# Motor_Control.net
KiCad netlist of a schematic drawn in Altium Designer
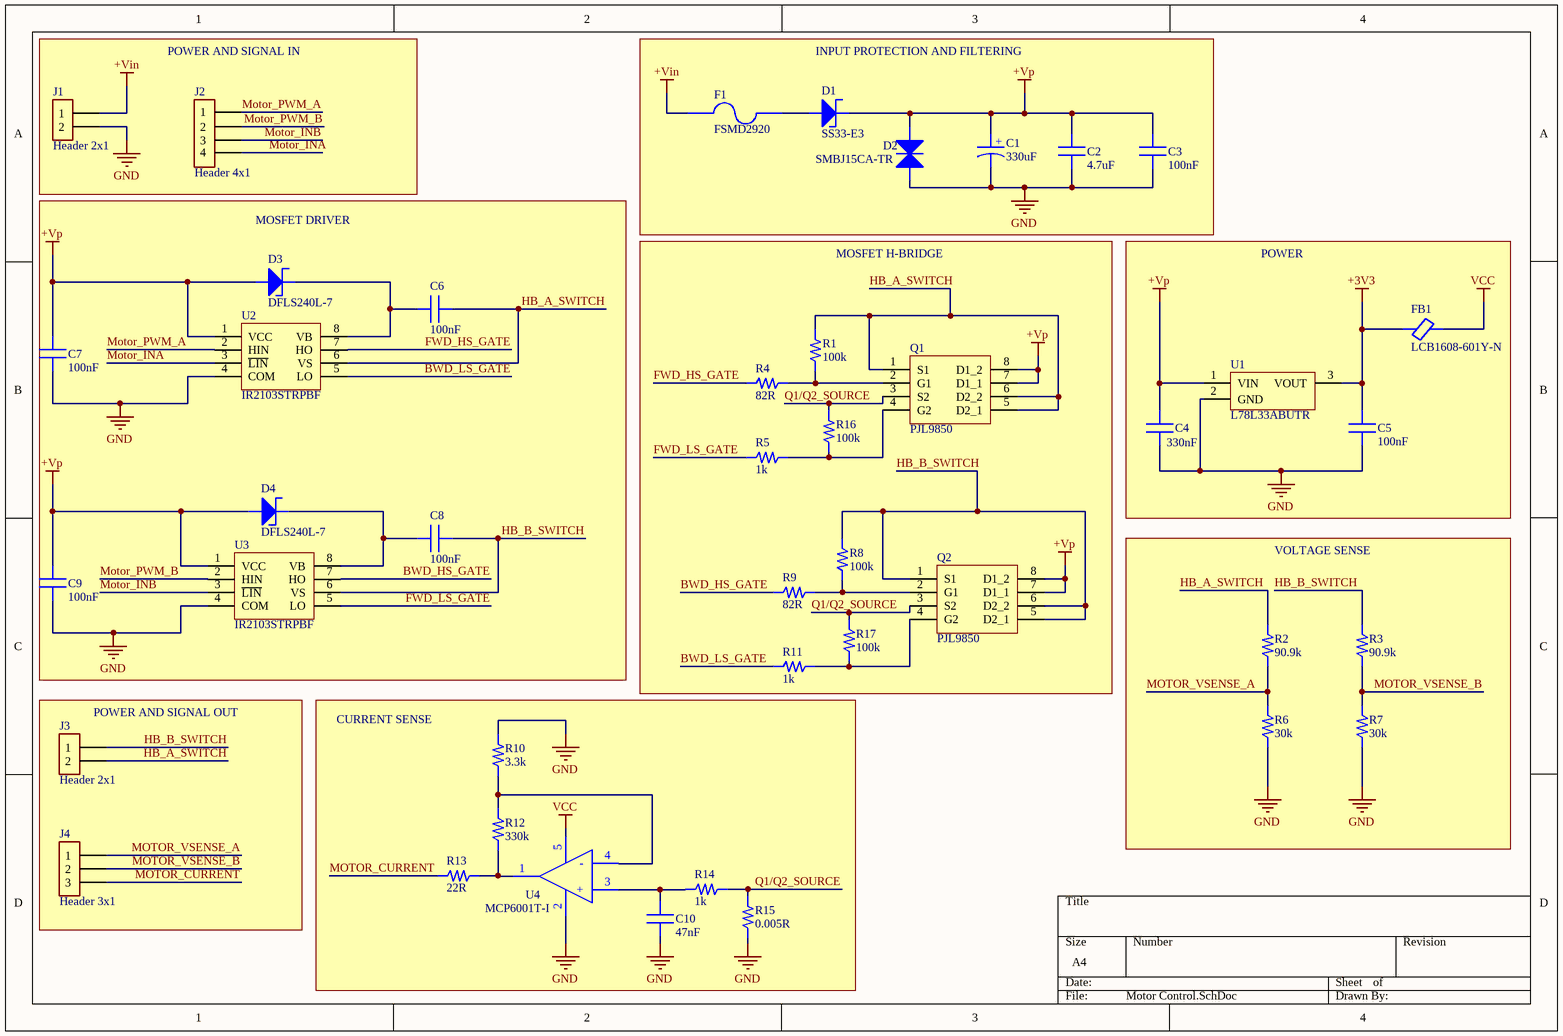
[diagram p0: Motor Control.SchDoc]

(export (version "E")
  (design (tool "Eeschema 10.0.6"))
  (components
    (comp (ref "C1")
      (value "330uF")
      (footprint "CAP_EEEFK1V331P")
      (description "330 µF 35 V Aluminum Electrolytic Capacitors Radial, Can - SMD 2000 Hrs @ 105°C")
      (fields (field (name "TOLERANCE") "±20%") (field (name "MANUFACTURER") "Panasonic Industry"))
      (libsource (lib "Chicken_Coop_Door_Main_Board_V3") (part "CAP Electrolytic EEE-FK1V331P"))
    )
    (comp (ref "C2")
      (value "4.7uF")
      (footprint "CAPC2012X145N 0805")
      (description "MLCC (2012) 0805 4.7uF 16VDC ±10% X7R AUTOMOTIVE")
      (fields (field (name "TOLERANCE") "±10 %") (field (name "MANUFACTURER") "SAMSUNG"))
      (libsource (lib "Chicken_Coop_Door_Main_Board_V3") (part "CAP 0805 4.7uF CL21B475KOQVPNE"))
    )
    (comp (ref "C3")
      (value "100nF")
      (footprint "CAPC2012X145N 0805")
      (description "MLCC 0805 100nF 50VDC ±10% X7R")
      (fields (field (name "TOLERANCE") "±5 %") (field (name "MANUFACTURER") "YAGEO"))
      (libsource (lib "Chicken_Coop_Door_Main_Board_V3") (part "CAP 0805 100nF CC0805JRX7R9BB104"))
    )
    (comp (ref "C4")
      (value "330nF")
      (footprint "CAPC2012X145N 0805")
      (description "MLCC (2012) 0805 330nF 50VDC ±10% X7R")
      (fields (field (name "TOLERANCE") "±10 %") (field (name "MANUFACTURER") "SAMSUNG"))
      (libsource (lib "Chicken_Coop_Door_Main_Board_V3") (part "CAP 0805 330nF CL21B334KBFNNNE"))
    )
    (comp (ref "C5")
      (value "100nF")
      (footprint "CAPC2012X145N 0805")
      (description "MLCC 0805 100nF 50VDC ±10% X7R")
      (fields (field (name "TOLERANCE") "±5 %") (field (name "MANUFACTURER") "YAGEO"))
      (libsource (lib "Chicken_Coop_Door_Main_Board_V3") (part "CAP 0805 100nF CC0805JRX7R9BB104"))
    )
    (comp (ref "C6")
      (value "100nF")
      (footprint "CAPC2012X145N 0805")
      (description "MLCC 0805 100nF 50VDC ±10% X7R")
      (fields (field (name "TOLERANCE") "±5 %") (field (name "MANUFACTURER") "YAGEO"))
      (libsource (lib "Chicken_Coop_Door_Main_Board_V3") (part "CAP 0805 100nF CC0805JRX7R9BB104"))
    )
    (comp (ref "C7")
      (value "100nF")
      (footprint "CAPC2012X145N 0805")
      (description "MLCC 0805 100nF 50VDC ±10% X7R")
      (fields (field (name "TOLERANCE") "±5 %") (field (name "MANUFACTURER") "YAGEO"))
      (libsource (lib "Chicken_Coop_Door_Main_Board_V3") (part "CAP 0805 100nF CC0805JRX7R9BB104"))
    )
    (comp (ref "C8")
      (value "100nF")
      (footprint "CAPC2012X145N 0805")
      (description "MLCC 0805 100nF 50VDC ±10% X7R")
      (fields (field (name "TOLERANCE") "±5 %") (field (name "MANUFACTURER") "YAGEO"))
      (libsource (lib "Chicken_Coop_Door_Main_Board_V3") (part "CAP 0805 100nF CC0805JRX7R9BB104"))
    )
    (comp (ref "C9")
      (value "100nF")
      (footprint "CAPC2012X145N 0805")
      (description "MLCC 0805 100nF 50VDC ±10% X7R")
      (fields (field (name "TOLERANCE") "±5 %") (field (name "MANUFACTURER") "YAGEO"))
      (libsource (lib "Chicken_Coop_Door_Main_Board_V3") (part "CAP 0805 100nF CC0805JRX7R9BB104"))
    )
    (comp (ref "C10")
      (value "47nF")
      (footprint "CAPC2012X145N 0805")
      (description "CL21B473KBCNNNC")
      (fields (field (name "TOLERANCE") "±10 %") (field (name "MANUFACTURER") "SAMSUNG"))
      (libsource (lib "Chicken_Coop_Door_Main_Board_V3") (part "CAP 0805 47nF CL21B473KBCNNNC"))
    )
    (comp (ref "D1")
      (value "SS33-E3")
      (footprint "SS33-E3/57T Schottky Diode")
      (description "DIODE SCHOTTKY 30V 3A DO214AB")
      (fields (field (name "MANUFACTURER") "Vishay General Semiconductor - Diodes Division"))
      (libsource (lib "Chicken_Coop_Door_Main_Board_V3") (part "DIODE SCHOTTKY SS33-E3/57T"))
    )
    (comp (ref "D2")
      (value "SMBJ15CA-TR")
      (footprint "TVS DIODE SMBJ15CA-TR")
      (description "24.4V Clamp 25.1A Ipp Tvs Diode Surface Mount SMB")
      (fields (field (name "MANUFACTURER") "STMicroelectronics"))
      (libsource (lib "Chicken_Coop_Door_Main_Board_V3") (part "TVS DIODE SMBJ15CA-TR"))
    )
    (comp (ref "D3")
      (value "DFLS240L-7")
      (footprint "DIODE DFLS240L-7  POWERDI 123")
      (description "DIODE SCHOTTK 40V 2A POWERDI 123")
      (fields (field (name "MANUFACTURER") "Diodes Incorporated"))
      (libsource (lib "Chicken_Coop_Door_Main_Board_V3") (part "DIODE SCHOTTKY DFLS240L-7"))
    )
    (comp (ref "D4")
      (value "DFLS240L-7")
      (footprint "DIODE DFLS240L-7  POWERDI 123")
      (description "DIODE SCHOTTK 40V 2A POWERDI 123")
      (fields (field (name "MANUFACTURER") "Diodes Incorporated"))
      (libsource (lib "Chicken_Coop_Door_Main_Board_V3") (part "DIODE SCHOTTKY DFLS240L-7"))
    )
    (comp (ref "F1")
      (value "FSMD2920")
      (footprint "FUSE FSMD200-24-2920-R")
      (description "PTC Resettable Fuse 24V 2 A Ih Surface Mount 2920 (7351 Metric), Concave")
      (fields (field (name "MANUFACTURER") "RFE/Fuzetec"))
      (libsource (lib "Chicken_Coop_Door_Main_Board_V3") (part "FUSE FSMD200-24-2920-R"))
    )
    (comp (ref "FB1")
      (value "LCB1608-601Y-N")
      (footprint "MPZ1608S601ATA00 0603 1608X95N")
      (description "600 Ohms @ 100 MHz 1 Power Line Ferrite Bead 0603 (1608 Metric) 1A 200mOhm")
      (fields (field (name "TOLERANCE") "±25 %") (field (name "MANUFACTURER") "CORE MASTER"))
      (libsource (lib "Chicken_Coop_Door_Main_Board_V3") (part "Ferrite Bead LCB1608-601Y-N"))
    )
    (comp (ref "J1")
      (value "Header 2x1")
      (footprint "2x1 Terminal Block")
      (description "TERM.BLK.5.00MM 2P PCB TYPE GREEN")
      (fields (field (name "MANUFACTURER") "DEGSON") (field (name "VOLTAGE") "300V"))
      (libsource (lib "Chicken_Coop_Door_Main_Board_V3") (part "Terminal Block 2x1"))
    )
    (comp (ref "J2")
      (value "Header 4x1")
      (footprint "JST_B4B-PH-K-S 1x4 Header")
      (description "CON.T.B.2MM 4P 180C MALE WHITE CONNFLY")
      (fields (field (name "MANUFACTURER") "CONNFLY"))
      (libsource (lib "Chicken_Coop_Door_Main_Board_V3") (part "Header 4x1 DS1066-4MVW6X"))
    )
    (comp (ref "J3")
      (value "Header 2x1")
      (footprint "2x1 Terminal Block")
      (description "TERM.BLK.5.00MM 2P PCB TYPE GREEN")
      (fields (field (name "MANUFACTURER") "DEGSON") (field (name "VOLTAGE") "300V"))
      (libsource (lib "Chicken_Coop_Door_Main_Board_V3") (part "Terminal Block 2x1"))
    )
    (comp (ref "J4")
      (value "Header 3x1")
      (footprint "JST_B3B-PH-K-S 1x3 Header")
      (description "CON.T.B.2.00MM 3P 180C MALE CONNFLY")
      (fields (field (name "MANUFACTURER") "CONNFLY"))
      (libsource (lib "Chicken_Coop_Door_Main_Board_V3") (part "Header 3x1 DS1066-3MVW6X"))
    )
    (comp (ref "Q1")
      (value "PJL9850")
      (footprint "PJL850 N-CH MOSFET")
      (description "Low Voltage MOSFET (20-40V,Rds(on)<1) - PJL9850 , N/N Channel, Dual, 5.4A, 40V, SOP-8")
      (fields (field (name "MANUFACTURER") "PANJIT"))
      (libsource (lib "Chicken_Coop_Door_Main_Board_V3") (part "PJL9850 N-Ch MOSFET"))
    )
    (comp (ref "Q2")
      (value "PJL9850")
      (footprint "PJL850 N-CH MOSFET")
      (description "Low Voltage MOSFET (20-40V,Rds(on)<1) - PJL9850 , N/N Channel, Dual, 5.4A, 40V, SOP-8")
      (fields (field (name "MANUFACTURER") "PANJIT"))
      (libsource (lib "Chicken_Coop_Door_Main_Board_V3") (part "PJL9850 N-Ch MOSFET"))
    )
    (comp (ref "R1")
      (value "100k")
      (footprint "RES 0603 ROYALOHM")
      (description "RES.(1608) 0603 100K Ohms 1% 1/10W-S 100PPM")
      (fields (field (name "TOLERANCE") "±5 %") (field (name "MANUFACTURER") "ROYALOHM"))
      (libsource (lib "Chicken_Coop_Door_Main_Board_V3") (part "RES 0603 100k 0603SAF1003T5E"))
    )
    (comp (ref "R2")
      (value "90.9k")
      (footprint "RES 0805 YAGEO C2012X60N")
      (description "RES.(2012) 0805 90.9K Ohms 1% 1/8W-S 100PPM")
      (fields (field (name "POWER") "1/8W") (field (name "TOLERANCE") "±1 %"))
      (libsource (lib "Chicken_Coop_Door_Main_Board_V3") (part "RES 0805 90.9k Ohms 0805S8F9092T5E"))
    )
    (comp (ref "R3")
      (value "90.9k")
      (footprint "RES 0805 YAGEO C2012X60N")
      (description "RES.(2012) 0805 90.9K Ohms 1% 1/8W-S 100PPM")
      (fields (field (name "POWER") "1/8W") (field (name "TOLERANCE") "±1 %"))
      (libsource (lib "Chicken_Coop_Door_Main_Board_V3") (part "RES 0805 90.9k Ohms 0805S8F9092T5E"))
    )
    (comp (ref "R4")
      (value "82R")
      (footprint "RES 0805 YAGEO C2012X60N")
      (description "RES.(2012) 0805 82 Ohms 5% 1/8W-S 200PPM")
      (fields (field (name "POWER") "1/8W") (field (name "TOLERANCE") "±1 %"))
      (libsource (lib "Chicken_Coop_Door_Main_Board_V3") (part "RES 0805 82 Ohms 0805S8J0820T5E"))
    )
    (comp (ref "R5")
      (value "1k")
      (footprint "RES 0805 YAGEO C2012X60N")
      (description "RES.(2012) 0805 1K Ohms 1% 1/8W-S 100PPM")
      (fields (field (name "POWER") "1/8W") (field (name "TOLERANCE") "±1 %"))
      (libsource (lib "Chicken_Coop_Door_Main_Board_V3") (part "RES 0805 1k Ohms 0805S8F1001TDE"))
    )
    (comp (ref "R6")
      (value "30k")
      (footprint "RES 0805 YAGEO C2012X60N")
      (description "RES.(2012) 0805 30K Ohms 1% 1/8W-S 100PPM")
      (fields (field (name "POWER") "1/8W") (field (name "TOLERANCE") "±1 %"))
      (libsource (lib "Chicken_Coop_Door_Main_Board_V3") (part "RES 0805 30k Ohms 0805S8F3002T5E"))
    )
    (comp (ref "R7")
      (value "30k")
      (footprint "RES 0805 YAGEO C2012X60N")
      (description "RES.(2012) 0805 30K Ohms 1% 1/8W-S 100PPM")
      (fields (field (name "POWER") "1/8W") (field (name "TOLERANCE") "±1 %"))
      (libsource (lib "Chicken_Coop_Door_Main_Board_V3") (part "RES 0805 30k Ohms 0805S8F3002T5E"))
    )
    (comp (ref "R8")
      (value "100k")
      (footprint "RES 0603 ROYALOHM")
      (description "RES.(1608) 0603 100K Ohms 1% 1/10W-S 100PPM")
      (fields (field (name "TOLERANCE") "±5 %") (field (name "MANUFACTURER") "ROYALOHM"))
      (libsource (lib "Chicken_Coop_Door_Main_Board_V3") (part "RES 0603 100k 0603SAF1003T5E"))
    )
    (comp (ref "R9")
      (value "82R")
      (footprint "RES 0805 YAGEO C2012X60N")
      (description "RES.(2012) 0805 82 Ohms 5% 1/8W-S 200PPM")
      (fields (field (name "POWER") "1/8W") (field (name "TOLERANCE") "±1 %"))
      (libsource (lib "Chicken_Coop_Door_Main_Board_V3") (part "RES 0805 82 Ohms 0805S8J0820T5E"))
    )
    (comp (ref "R10")
      (value "3.3k")
      (footprint "RES 0805 YAGEO C2012X60N")
      (description "RES.(2012) 0805 3.3K Ohms 1% 1/8W-S 100PPM")
      (fields (field (name "POWER") "1/8W") (field (name "TOLERANCE") "±1 %"))
      (libsource (lib "Chicken_Coop_Door_Main_Board_V3") (part "RES 0805 3.3k Ohms 0805S8F3301TDE"))
    )
    (comp (ref "R11")
      (value "1k")
      (footprint "RES 0805 YAGEO C2012X60N")
      (description "RES.(2012) 0805 1K Ohms 1% 1/8W-S 100PPM")
      (fields (field (name "POWER") "1/8W") (field (name "TOLERANCE") "±1 %"))
      (libsource (lib "Chicken_Coop_Door_Main_Board_V3") (part "RES 0805 1k Ohms 0805S8F1001TDE"))
    )
    (comp (ref "R12")
      (value "330k")
      (footprint "RES 0603 ROYALOHM")
      (description "RES.(1608) 0603 330K Ohms 1% 1/10W-S 100PPM")
      (fields (field (name "TOLERANCE") "±5 %") (field (name "MANUFACTURER") "ROYALOHM"))
      (libsource (lib "Chicken_Coop_Door_Main_Board_V3") (part "RES 0603 330k 0603SAF3303T5E"))
    )
    (comp (ref "R13")
      (value "22R")
      (footprint "RES 0603 ROYALOHM")
      (description "RES.(1608) 0603 22 Ohms 5% 1/10W-S 200PPM")
      (fields (field (name "TOLERANCE") "±5%") (field (name "MANUFACTURER") "ROYALOHM"))
      (libsource (lib "Chicken_Coop_Door_Main_Board_V3") (part "RES 0603 22 Ohms 0603SAJ0220T5E"))
    )
    (comp (ref "R14")
      (value "1k")
      (footprint "RES 0805 YAGEO C2012X60N")
      (description "RES.(2012) 0805 1K Ohms 1% 1/8W-S 100PPM")
      (fields (field (name "POWER") "1/8W") (field (name "TOLERANCE") "±1 %"))
      (libsource (lib "Chicken_Coop_Door_Main_Board_V3") (part "RES 0805 1k Ohms 0805S8F1001TDE"))
    )
    (comp (ref "R15")
      (value "0.005R")
      (footprint "RES 1206 YAGEO")
      (description "RES.(3216) 1206 5m Ohms 1% 1/4W 100PPM AEC-Q200 SM")
      (fields (field (name "POWER") "1/4W") (field (name "TOLERANCE") "±1 %"))
      (libsource (lib "Chicken_Coop_Door_Main_Board_V3") (part "RES 1206 5 mOhms PE1206FRF070R005L"))
    )
    (comp (ref "R16")
      (value "100k")
      (footprint "RES 0603 ROYALOHM")
      (description "RES.(1608) 0603 100K Ohms 1% 1/10W-S 100PPM")
      (fields (field (name "TOLERANCE") "±5 %") (field (name "MANUFACTURER") "ROYALOHM"))
      (libsource (lib "Chicken_Coop_Door_Main_Board_V3") (part "RES 0603 100k 0603SAF1003T5E"))
    )
    (comp (ref "R17")
      (value "100k")
      (footprint "RES 0603 ROYALOHM")
      (description "RES.(1608) 0603 100K Ohms 1% 1/10W-S 100PPM")
      (fields (field (name "TOLERANCE") "±5 %") (field (name "MANUFACTURER") "ROYALOHM"))
      (libsource (lib "Chicken_Coop_Door_Main_Board_V3") (part "RES 0603 100k 0603SAF1003T5E"))
    )
    (comp (ref "U1")
      (value "L78L33ABUTR")
      (footprint "LDO L78L33ABUTR SOT89")
      (description "Linear Voltage Regulator IC Positive Fixed 1 Output 100mA SOT-89-3")
      (fields (field (name "MANUFACTURER") "STMicroelectronics"))
      (libsource (lib "Chicken_Coop_Door_Main_Board_V3") (part "LDO L78L33ABUTR"))
    )
    (comp (ref "U2")
      (value "IR2103STRPBF")
      (footprint "IR2103STRPBF Half Bridge Mosfet Driver")
      (description "Half-Bridge Gate Driver IC Inverting, Non-Inverting 8-SOIC")
      (fields (field (name "MANUFACTURER") "Infineon Technologies"))
      (libsource (lib "Chicken_Coop_Door_Main_Board_V3") (part "IR2103STRPBF Half Bridge MOSFET Driver"))
    )
    (comp (ref "U3")
      (value "IR2103STRPBF")
      (footprint "IR2103STRPBF Half Bridge Mosfet Driver")
      (description "Half-Bridge Gate Driver IC Inverting, Non-Inverting 8-SOIC")
      (fields (field (name "MANUFACTURER") "Infineon Technologies"))
      (libsource (lib "Chicken_Coop_Door_Main_Board_V3") (part "IR2103STRPBF Half Bridge MOSFET Driver"))
    )
    (comp (ref "U4")
      (value "MCP6001T-I")
      (footprint "MCP6001T-I/OT OPAMP SOT-23-5")
      (description "Standard (General Purpose) Amplifier 1 Circuit Rail-to-Rail SOT-23-5")
      (fields (field (name "MANUFACTURER") "Microchip Technology"))
      (libsource (lib "Chicken_Coop_Door_Main_Board_V3") (part "MCP6001T-I/OT OP-AMP 1 CH LOW POWER"))
    )
  )
  (nets
    (net (code "1") (name "+3V3") (class "Default")
      (node (ref "C5") (pin "2") (pinfunction "2_2") (pintype "passive"))
      (node (ref "FB1") (pin "1") (pinfunction "1_1") (pintype "passive"))
      (node (ref "U1") (pin "3") (pinfunction "VOUT_3") (pintype "passive"))
    )
    (net (code "2") (name "+Vin") (class "Default")
      (node (ref "F1") (pin "1") (pinfunction "1_1") (pintype "passive"))
      (node (ref "J1") (pin "1") (pinfunction "1_1") (pintype "passive"))
    )
    (net (code "3") (name "+Vp") (class "Default")
      (node (ref "C1") (pin "1") (pinfunction "1_1") (pintype "passive"))
      (node (ref "C2") (pin "2") (pinfunction "2_2") (pintype "passive"))
      (node (ref "C3") (pin "2") (pinfunction "2_2") (pintype "passive"))
      (node (ref "C4") (pin "2") (pinfunction "2_2") (pintype "passive"))
      (node (ref "C7") (pin "2") (pinfunction "2_2") (pintype "passive"))
      (node (ref "C9") (pin "2") (pinfunction "2_2") (pintype "passive"))
      (node (ref "D1") (pin "K") (pinfunction "Cathode_K") (pintype "passive"))
      (node (ref "D2") (pin "2") (pinfunction "C_2") (pintype "passive"))
      (node (ref "D3") (pin "1") (pinfunction "Anode_1") (pintype "passive"))
      (node (ref "D4") (pin "1") (pinfunction "Anode_1") (pintype "passive"))
      (node (ref "Q1") (pin "7") (pinfunction "D1_1_7") (pintype "passive"))
      (node (ref "Q1") (pin "8") (pinfunction "D1_2_8") (pintype "passive"))
      (node (ref "Q2") (pin "7") (pinfunction "D1_1_7") (pintype "passive"))
      (node (ref "Q2") (pin "8") (pinfunction "D1_2_8") (pintype "passive"))
      (node (ref "U1") (pin "1") (pinfunction "VIN_1") (pintype "passive"))
      (node (ref "U2") (pin "1") (pinfunction "VCC_1") (pintype "passive"))
      (node (ref "U3") (pin "1") (pinfunction "VCC_1") (pintype "passive"))
    )
    (net (code "4") (name "/BWD_HS_GATE") (class "Default")
      (node (ref "R9") (pin "1") (pinfunction "1_1") (pintype "passive"))
      (node (ref "U3") (pin "7") (pinfunction "HO_7") (pintype "passive"))
    )
    (net (code "5") (name "/BWD_LS_GATE") (class "Default")
      (node (ref "R11") (pin "1") (pinfunction "1_1") (pintype "passive"))
      (node (ref "U2") (pin "5") (pinfunction "LO_5") (pintype "passive"))
    )
    (net (code "6") (name "/FWD_HS_GATE") (class "Default")
      (node (ref "R4") (pin "1") (pinfunction "1_1") (pintype "passive"))
      (node (ref "U2") (pin "7") (pinfunction "HO_7") (pintype "passive"))
    )
    (net (code "7") (name "/FWD_LS_GATE") (class "Default")
      (node (ref "R5") (pin "1") (pinfunction "1_1") (pintype "passive"))
      (node (ref "U3") (pin "5") (pinfunction "LO_5") (pintype "passive"))
    )
    (net (code "8") (name "/HB_A_SWITCH") (class "Default")
      (node (ref "C6") (pin "1") (pinfunction "1_1") (pintype "passive"))
      (node (ref "J3") (pin "2") (pinfunction "2_2") (pintype "passive"))
      (node (ref "Q1") (pin "1") (pinfunction "S1_1") (pintype "passive"))
      (node (ref "Q1") (pin "5") (pinfunction "D2_1_5") (pintype "passive"))
      (node (ref "Q1") (pin "6") (pinfunction "D2_2_6") (pintype "passive"))
      (node (ref "R1") (pin "2") (pinfunction "2_2") (pintype "passive"))
      (node (ref "R2") (pin "2") (pinfunction "2_2") (pintype "passive"))
      (node (ref "U2") (pin "6") (pinfunction "VS_6") (pintype "passive"))
    )
    (net (code "9") (name "/HB_B_SWITCH") (class "Default")
      (node (ref "C8") (pin "1") (pinfunction "1_1") (pintype "passive"))
      (node (ref "J3") (pin "1") (pinfunction "1_1") (pintype "passive"))
      (node (ref "Q2") (pin "1") (pinfunction "S1_1") (pintype "passive"))
      (node (ref "Q2") (pin "5") (pinfunction "D2_1_5") (pintype "passive"))
      (node (ref "Q2") (pin "6") (pinfunction "D2_2_6") (pintype "passive"))
      (node (ref "R3") (pin "2") (pinfunction "2_2") (pintype "passive"))
      (node (ref "R8") (pin "2") (pinfunction "2_2") (pintype "passive"))
      (node (ref "U3") (pin "6") (pinfunction "VS_6") (pintype "passive"))
    )
    (net (code "10") (name "/MOTOR_CURRENT") (class "Default")
      (node (ref "J4") (pin "3") (pinfunction "3_3") (pintype "passive"))
      (node (ref "R13") (pin "2") (pinfunction "2_2") (pintype "passive"))
    )
    (net (code "11") (name "/MOTOR_VSENSE_A") (class "Default")
      (node (ref "J4") (pin "1") (pinfunction "1_1") (pintype "passive"))
      (node (ref "R2") (pin "1") (pinfunction "1_1") (pintype "passive"))
      (node (ref "R6") (pin "2") (pinfunction "2_2") (pintype "passive"))
    )
    (net (code "12") (name "/MOTOR_VSENSE_B") (class "Default")
      (node (ref "J4") (pin "2") (pinfunction "2_2") (pintype "passive"))
      (node (ref "R3") (pin "1") (pinfunction "1_1") (pintype "passive"))
      (node (ref "R7") (pin "2") (pinfunction "2_2") (pintype "passive"))
    )
    (net (code "13") (name "/Motor_INA") (class "Default")
      (node (ref "J2") (pin "4") (pinfunction "4_4") (pintype "passive"))
      (node (ref "U2") (pin "3") (pinfunction "~{LIN}_3") (pintype "passive"))
    )
    (net (code "14") (name "/Motor_INB") (class "Default")
      (node (ref "J2") (pin "3") (pinfunction "3_3") (pintype "passive"))
      (node (ref "U3") (pin "3") (pinfunction "~{LIN}_3") (pintype "passive"))
    )
    (net (code "15") (name "/Motor_PWM_A") (class "Default")
      (node (ref "J2") (pin "1") (pinfunction "1_1") (pintype "passive"))
      (node (ref "U2") (pin "2") (pinfunction "HIN_2") (pintype "passive"))
    )
    (net (code "16") (name "/Motor_PWM_B") (class "Default")
      (node (ref "J2") (pin "2") (pinfunction "2_2") (pintype "passive"))
      (node (ref "U3") (pin "2") (pinfunction "HIN_2") (pintype "passive"))
    )
    (net (code "17") (name "/Q1{slash}Q2_SOURCE") (class "Default")
      (node (ref "Q1") (pin "3") (pinfunction "S2_3") (pintype "passive"))
      (node (ref "Q2") (pin "3") (pinfunction "S2_3") (pintype "passive"))
      (node (ref "R14") (pin "1") (pinfunction "1_1") (pintype "passive"))
      (node (ref "R15") (pin "2") (pinfunction "2_2") (pintype "passive"))
      (node (ref "R16") (pin "2") (pinfunction "2_2") (pintype "passive"))
      (node (ref "R17") (pin "2") (pinfunction "2_2") (pintype "passive"))
    )
    (net (code "18") (name "GND") (class "Default")
      (node (ref "C1") (pin "2") (pinfunction "2_2") (pintype "passive"))
      (node (ref "C10") (pin "1") (pinfunction "1_1") (pintype "passive"))
      (node (ref "C2") (pin "1") (pinfunction "1_1") (pintype "passive"))
      (node (ref "C3") (pin "1") (pinfunction "1_1") (pintype "passive"))
      (node (ref "C4") (pin "1") (pinfunction "1_1") (pintype "passive"))
      (node (ref "C5") (pin "1") (pinfunction "1_1") (pintype "passive"))
      (node (ref "C7") (pin "1") (pinfunction "1_1") (pintype "passive"))
      (node (ref "C9") (pin "1") (pinfunction "1_1") (pintype "passive"))
      (node (ref "D2") (pin "1") (pinfunction "A_1") (pintype "passive"))
      (node (ref "J1") (pin "2") (pinfunction "2_2") (pintype "passive"))
      (node (ref "R10") (pin "2") (pinfunction "2_2") (pintype "passive"))
      (node (ref "R15") (pin "1") (pinfunction "1_1") (pintype "passive"))
      (node (ref "R6") (pin "1") (pinfunction "1_1") (pintype "passive"))
      (node (ref "R7") (pin "1") (pinfunction "1_1") (pintype "passive"))
      (node (ref "U1") (pin "2") (pinfunction "GND_2") (pintype "passive"))
      (node (ref "U2") (pin "4") (pinfunction "COM_4") (pintype "passive"))
      (node (ref "U3") (pin "4") (pinfunction "COM_4") (pintype "passive"))
      (node (ref "U4") (pin "2") (pinfunction "VSS_2") (pintype "passive"))
    )
    (net (code "19") (name "Net-(D1-Anode)") (class "Default")
      (node (ref "D1") (pin "A") (pinfunction "Anode_A") (pintype "passive"))
      (node (ref "F1") (pin "2") (pinfunction "2_2") (pintype "passive"))
    )
    (net (code "20") (name "Net-(D3-Cathode)") (class "Default")
      (node (ref "C6") (pin "2") (pinfunction "2_2") (pintype "passive"))
      (node (ref "D3") (pin "2") (pinfunction "Cathode_2") (pintype "passive"))
      (node (ref "U2") (pin "8") (pinfunction "VB_8") (pintype "passive"))
    )
    (net (code "21") (name "Net-(D4-Cathode)") (class "Default")
      (node (ref "C8") (pin "2") (pinfunction "2_2") (pintype "passive"))
      (node (ref "D4") (pin "2") (pinfunction "Cathode_2") (pintype "passive"))
      (node (ref "U3") (pin "8") (pinfunction "VB_8") (pintype "passive"))
    )
    (net (code "22") (name "Net-(Q1-G1)") (class "Default")
      (node (ref "Q1") (pin "2") (pinfunction "G1_2") (pintype "passive"))
      (node (ref "R1") (pin "1") (pinfunction "1_1") (pintype "passive"))
      (node (ref "R4") (pin "2") (pinfunction "2_2") (pintype "passive"))
    )
    (net (code "23") (name "Net-(Q1-G2)") (class "Default")
      (node (ref "Q1") (pin "4") (pinfunction "G2_4") (pintype "passive"))
      (node (ref "R16") (pin "1") (pinfunction "1_1") (pintype "passive"))
      (node (ref "R5") (pin "2") (pinfunction "2_2") (pintype "passive"))
    )
    (net (code "24") (name "Net-(Q2-G1)") (class "Default")
      (node (ref "Q2") (pin "2") (pinfunction "G1_2") (pintype "passive"))
      (node (ref "R8") (pin "1") (pinfunction "1_1") (pintype "passive"))
      (node (ref "R9") (pin "2") (pinfunction "2_2") (pintype "passive"))
    )
    (net (code "25") (name "Net-(Q2-G2)") (class "Default")
      (node (ref "Q2") (pin "4") (pinfunction "G2_4") (pintype "passive"))
      (node (ref "R11") (pin "2") (pinfunction "2_2") (pintype "passive"))
      (node (ref "R17") (pin "1") (pinfunction "1_1") (pintype "passive"))
    )
    (net (code "26") (name "Net-(U4-+)") (class "Default")
      (node (ref "C10") (pin "2") (pinfunction "2_2") (pintype "passive"))
      (node (ref "R14") (pin "2") (pinfunction "2_2") (pintype "passive"))
      (node (ref "U4") (pin "3") (pinfunction "+_3") (pintype "passive"))
    )
    (net (code "27") (name "Net-(U4--)") (class "Default")
      (node (ref "R10") (pin "1") (pinfunction "1_1") (pintype "passive"))
      (node (ref "R12") (pin "2") (pinfunction "2_2") (pintype "passive"))
      (node (ref "U4") (pin "4") (pinfunction "-_4") (pintype "passive"))
    )
    (net (code "28") (name "Net-(U4-Vout)") (class "Default")
      (node (ref "R12") (pin "1") (pinfunction "1_1") (pintype "passive"))
      (node (ref "R13") (pin "1") (pinfunction "1_1") (pintype "passive"))
      (node (ref "U4") (pin "1") (pinfunction "Vout_1") (pintype "passive"))
    )
    (net (code "29") (name "VCC") (class "Default")
      (node (ref "FB1") (pin "2") (pinfunction "2_2") (pintype "passive"))
      (node (ref "U4") (pin "5") (pinfunction "VDD_5") (pintype "passive"))
    )
  )
)
